# Public_QSGMII_ETHERNET_POWER.net
KiCad netlist of a schematic drawn in Altium Designer
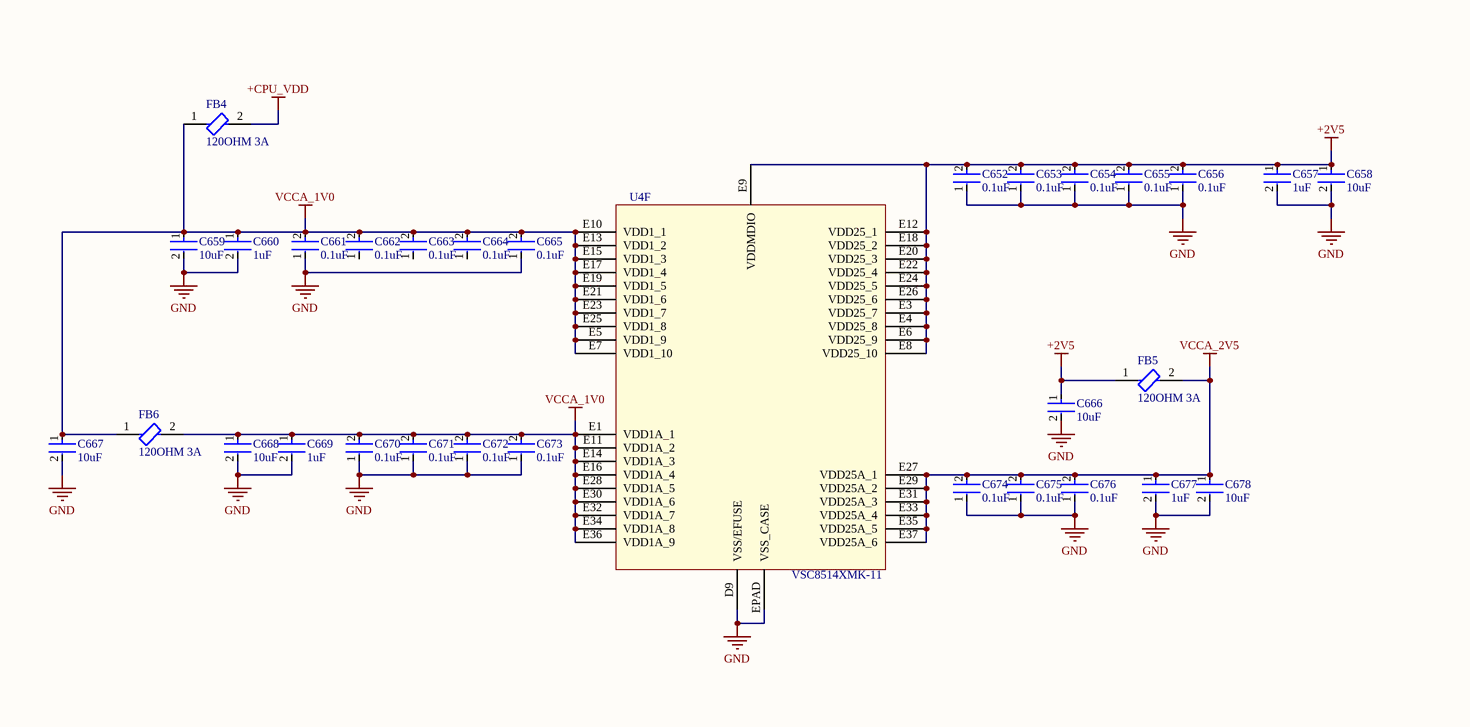
[diagram p0: Public_QSGMII_ETHERNET_POWER.SchDoc, left]
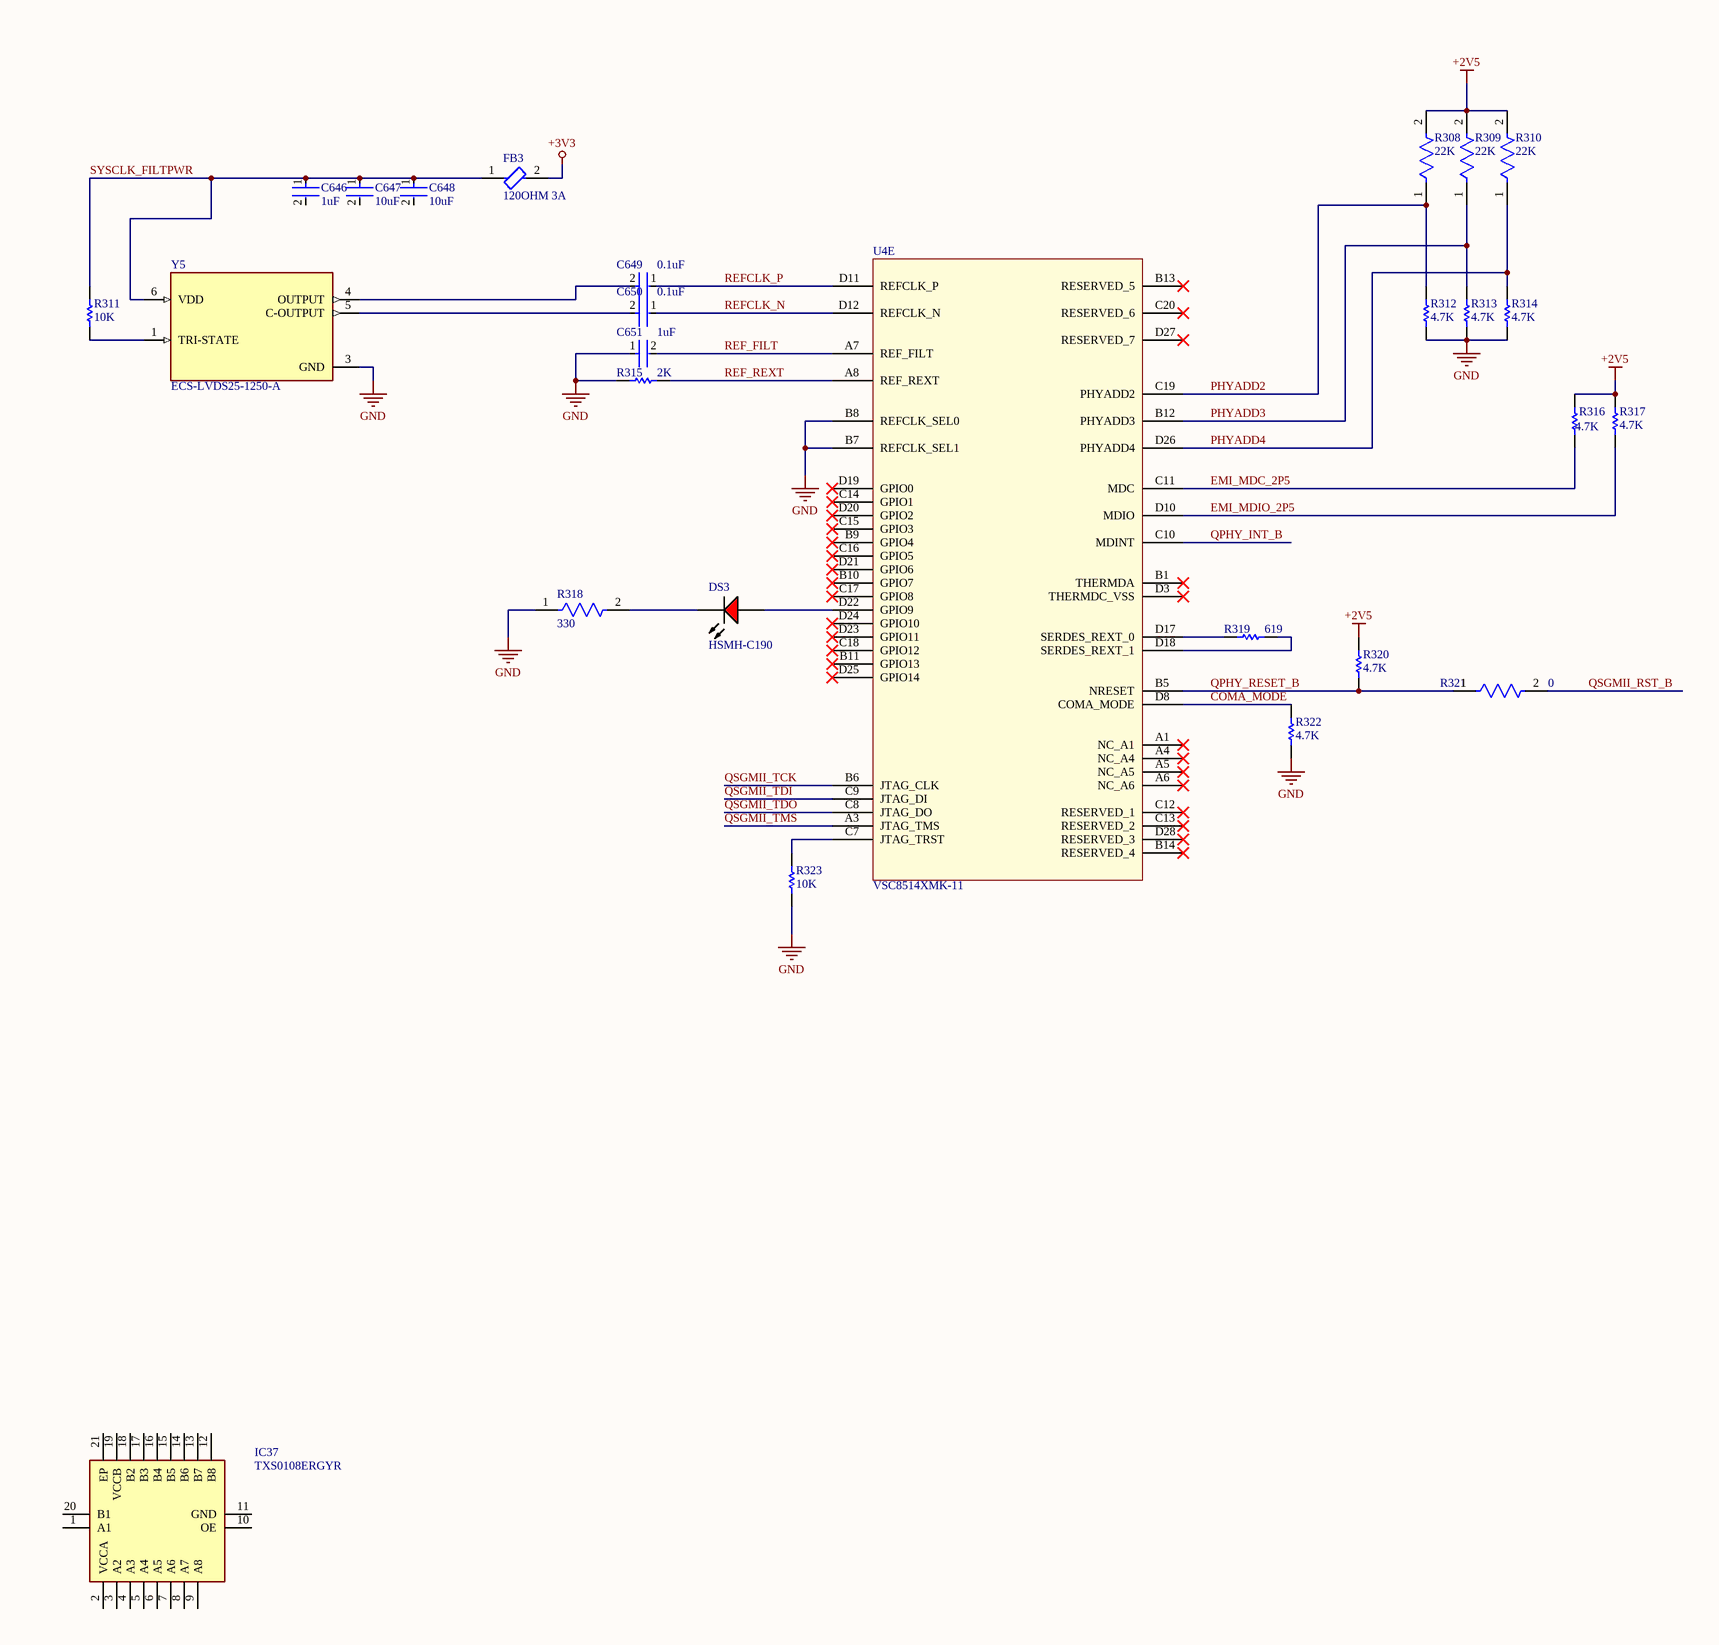
[diagram p1: Public_QSGMII_ETHERNET_POWER.SchDoc, right]

(export (version "E")
  (design (tool "Eeschema 10.0.6"))
  (components
    (comp (ref "C646")
      (value "1uF")
      (footprint "FP-GRM15-0_1-MFG")
      (description "CAP CER 1UF 10V X5R 0402")
      (fields
        (field (name "OCTOPART") "https://octopart.com/grm155r61a105ke15d-murata-197442")
        (field (name "MANUFACTURER PART NUMBER") "GRM155R61A105KE15D")
      )
      (libsource (lib "Altium Content Vault") (part "02cd4be3c70576c341d710602a673aa"))
    )
    (comp (ref "C647")
      (value "10uF")
      (footprint "FP-C0805C-DG-MFG")
      (description "CAP CER 10UF 10V X5R 0805")
      (fields (field (name "TOLERANCE") "10%") (field (name "MANUFACTURER PART NUMBER") "C0805C106K8PACTU"))
      (libsource (lib "Altium Content Vault") (part "11868f565c42a9108669ba33697ecf6"))
    )
    (comp (ref "C648")
      (value "10uF")
      (footprint "FP-C0805C-DG-MFG")
      (description "CAP CER 10UF 10V X5R 0805")
      (fields (field (name "TOLERANCE") "10%") (field (name "MANUFACTURER PART NUMBER") "C0805C106K8PACTU"))
      (libsource (lib "Altium Content Vault") (part "11868f565c42a9108669ba33697ecf6"))
    )
    (comp (ref "C649")
      (value "0.1uF")
      (footprint "FP-GRM15-MFG")
      (description "CAP CER 0.1UF 16V X7R 0402")
      (fields (field (name "MANUFACTURER PART NUMBER") "GRM155R71C104KA88D") (field (name "TOLERANCE") "10%"))
      (libsource (lib "Altium Content Vault") (part "236180d848d6139a670b325ea6854c9"))
    )
    (comp (ref "C650")
      (value "0.1uF")
      (footprint "FP-GRM15-MFG")
      (description "CAP CER 0.1UF 16V X7R 0402")
      (fields (field (name "MANUFACTURER PART NUMBER") "GRM155R71C104KA88D") (field (name "TOLERANCE") "10%"))
      (libsource (lib "Altium Content Vault") (part "236180d848d6139a670b325ea6854c9"))
    )
    (comp (ref "C651")
      (value "1uF")
      (footprint "FP-GRM15-0_1-MFG")
      (description "CAP CER 1UF 10V X5R 0402")
      (fields
        (field (name "OCTOPART") "https://octopart.com/grm155r61a105ke15d-murata-197442")
        (field (name "MANUFACTURER PART NUMBER") "GRM155R61A105KE15D")
      )
      (libsource (lib "Altium Content Vault") (part "02cd4be3c70576c341d710602a673aa"))
    )
    (comp (ref "C652")
      (value "0.1uF")
      (footprint "FP-GRM15-MFG")
      (description "CAP CER 0.1UF 16V X7R 0402")
      (fields (field (name "MANUFACTURER PART NUMBER") "GRM155R71C104KA88D") (field (name "TOLERANCE") "10%"))
      (libsource (lib "Altium Content Vault") (part "236180d848d6139a670b325ea6854c9"))
    )
    (comp (ref "C653")
      (value "0.1uF")
      (footprint "FP-GRM15-MFG")
      (description "CAP CER 0.1UF 16V X7R 0402")
      (fields (field (name "MANUFACTURER PART NUMBER") "GRM155R71C104KA88D") (field (name "TOLERANCE") "10%"))
      (libsource (lib "Altium Content Vault") (part "236180d848d6139a670b325ea6854c9"))
    )
    (comp (ref "C654")
      (value "0.1uF")
      (footprint "FP-GRM15-MFG")
      (description "CAP CER 0.1UF 16V X7R 0402")
      (fields (field (name "MANUFACTURER PART NUMBER") "GRM155R71C104KA88D") (field (name "TOLERANCE") "10%"))
      (libsource (lib "Altium Content Vault") (part "236180d848d6139a670b325ea6854c9"))
    )
    (comp (ref "C655")
      (value "0.1uF")
      (footprint "FP-GRM15-MFG")
      (description "CAP CER 0.1UF 16V X7R 0402")
      (fields (field (name "MANUFACTURER PART NUMBER") "GRM155R71C104KA88D") (field (name "TOLERANCE") "10%"))
      (libsource (lib "Altium Content Vault") (part "236180d848d6139a670b325ea6854c9"))
    )
    (comp (ref "C656")
      (value "0.1uF")
      (footprint "FP-GRM15-MFG")
      (description "CAP CER 0.1UF 16V X7R 0402")
      (fields (field (name "MANUFACTURER PART NUMBER") "GRM155R71C104KA88D") (field (name "TOLERANCE") "10%"))
      (libsource (lib "Altium Content Vault") (part "236180d848d6139a670b325ea6854c9"))
    )
    (comp (ref "C657")
      (value "1uF")
      (footprint "FP-GRM15-0_1-MFG")
      (description "CAP CER 1UF 10V X5R 0402")
      (fields
        (field (name "OCTOPART") "https://octopart.com/grm155r61a105ke15d-murata-197442")
        (field (name "MANUFACTURER PART NUMBER") "GRM155R61A105KE15D")
      )
      (libsource (lib "Altium Content Vault") (part "02cd4be3c70576c341d710602a673aa"))
    )
    (comp (ref "C658")
      (value "10uF")
      (footprint "FP-C0805C-DG-MFG")
      (description "CAP CER 10UF 10V X5R 0805")
      (fields (field (name "TOLERANCE") "10%") (field (name "MANUFACTURER PART NUMBER") "C0805C106K8PACTU"))
      (libsource (lib "Altium Content Vault") (part "11868f565c42a9108669ba33697ecf6"))
    )
    (comp (ref "C659")
      (value "10uF")
      (footprint "FP-C0805C-DG-MFG")
      (description "CAP CER 10UF 10V X5R 0805")
      (fields (field (name "TOLERANCE") "10%") (field (name "MANUFACTURER PART NUMBER") "C0805C106K8PACTU"))
      (libsource (lib "Altium Content Vault") (part "11868f565c42a9108669ba33697ecf6"))
    )
    (comp (ref "C660")
      (value "1uF")
      (footprint "FP-GRM15-0_1-MFG")
      (description "CAP CER 1UF 10V X5R 0402")
      (fields
        (field (name "OCTOPART") "https://octopart.com/grm155r61a105ke15d-murata-197442")
        (field (name "MANUFACTURER PART NUMBER") "GRM155R61A105KE15D")
      )
      (libsource (lib "Altium Content Vault") (part "02cd4be3c70576c341d710602a673aa"))
    )
    (comp (ref "C661")
      (value "0.1uF")
      (footprint "FP-GRM15-MFG")
      (description "CAP CER 0.1UF 16V X7R 0402")
      (fields (field (name "MANUFACTURER PART NUMBER") "GRM155R71C104KA88D") (field (name "TOLERANCE") "10%"))
      (libsource (lib "Altium Content Vault") (part "236180d848d6139a670b325ea6854c9"))
    )
    (comp (ref "C662")
      (value "0.1uF")
      (footprint "FP-GRM15-MFG")
      (description "CAP CER 0.1UF 16V X7R 0402")
      (fields (field (name "MANUFACTURER PART NUMBER") "GRM155R71C104KA88D") (field (name "TOLERANCE") "10%"))
      (libsource (lib "Altium Content Vault") (part "236180d848d6139a670b325ea6854c9"))
    )
    (comp (ref "C663")
      (value "0.1uF")
      (footprint "FP-GRM15-MFG")
      (description "CAP CER 0.1UF 16V X7R 0402")
      (fields (field (name "MANUFACTURER PART NUMBER") "GRM155R71C104KA88D") (field (name "TOLERANCE") "10%"))
      (libsource (lib "Altium Content Vault") (part "236180d848d6139a670b325ea6854c9"))
    )
    (comp (ref "C664")
      (value "0.1uF")
      (footprint "FP-GRM15-MFG")
      (description "CAP CER 0.1UF 16V X7R 0402")
      (fields (field (name "MANUFACTURER PART NUMBER") "GRM155R71C104KA88D") (field (name "TOLERANCE") "10%"))
      (libsource (lib "Altium Content Vault") (part "236180d848d6139a670b325ea6854c9"))
    )
    (comp (ref "C665")
      (value "0.1uF")
      (footprint "FP-GRM15-MFG")
      (description "CAP CER 0.1UF 16V X7R 0402")
      (fields (field (name "MANUFACTURER PART NUMBER") "GRM155R71C104KA88D") (field (name "TOLERANCE") "10%"))
      (libsource (lib "Altium Content Vault") (part "236180d848d6139a670b325ea6854c9"))
    )
    (comp (ref "C666")
      (value "10uF")
      (footprint "FP-C0805C-DG-MFG")
      (description "CAP CER 10UF 10V X5R 0805")
      (fields (field (name "TOLERANCE") "10%") (field (name "MANUFACTURER PART NUMBER") "C0805C106K8PACTU"))
      (libsource (lib "Altium Content Vault") (part "11868f565c42a9108669ba33697ecf6"))
    )
    (comp (ref "C667")
      (value "10uF")
      (footprint "FP-C0805C-DG-MFG")
      (description "CAP CER 10UF 10V X5R 0805")
      (fields (field (name "TOLERANCE") "10%") (field (name "MANUFACTURER PART NUMBER") "C0805C106K8PACTU"))
      (libsource (lib "Altium Content Vault") (part "11868f565c42a9108669ba33697ecf6"))
    )
    (comp (ref "C668")
      (value "10uF")
      (footprint "FP-C0805C-DG-MFG")
      (description "CAP CER 10UF 10V X5R 0805")
      (fields (field (name "TOLERANCE") "10%") (field (name "MANUFACTURER PART NUMBER") "C0805C106K8PACTU"))
      (libsource (lib "Altium Content Vault") (part "11868f565c42a9108669ba33697ecf6"))
    )
    (comp (ref "C669")
      (value "1uF")
      (footprint "FP-GRM15-0_1-MFG")
      (description "CAP CER 1UF 10V X5R 0402")
      (fields
        (field (name "OCTOPART") "https://octopart.com/grm155r61a105ke15d-murata-197442")
        (field (name "MANUFACTURER PART NUMBER") "GRM155R61A105KE15D")
      )
      (libsource (lib "Altium Content Vault") (part "02cd4be3c70576c341d710602a673aa"))
    )
    (comp (ref "C670")
      (value "0.1uF")
      (footprint "FP-GRM15-MFG")
      (description "CAP CER 0.1UF 16V X7R 0402")
      (fields (field (name "MANUFACTURER PART NUMBER") "GRM155R71C104KA88D") (field (name "TOLERANCE") "10%"))
      (libsource (lib "Altium Content Vault") (part "236180d848d6139a670b325ea6854c9"))
    )
    (comp (ref "C671")
      (value "0.1uF")
      (footprint "FP-GRM15-MFG")
      (description "CAP CER 0.1UF 16V X7R 0402")
      (fields (field (name "MANUFACTURER PART NUMBER") "GRM155R71C104KA88D") (field (name "TOLERANCE") "10%"))
      (libsource (lib "Altium Content Vault") (part "236180d848d6139a670b325ea6854c9"))
    )
    (comp (ref "C672")
      (value "0.1uF")
      (footprint "FP-GRM15-MFG")
      (description "CAP CER 0.1UF 16V X7R 0402")
      (fields (field (name "MANUFACTURER PART NUMBER") "GRM155R71C104KA88D") (field (name "TOLERANCE") "10%"))
      (libsource (lib "Altium Content Vault") (part "236180d848d6139a670b325ea6854c9"))
    )
    (comp (ref "C673")
      (value "0.1uF")
      (footprint "FP-GRM15-MFG")
      (description "CAP CER 0.1UF 16V X7R 0402")
      (fields (field (name "MANUFACTURER PART NUMBER") "GRM155R71C104KA88D") (field (name "TOLERANCE") "10%"))
      (libsource (lib "Altium Content Vault") (part "236180d848d6139a670b325ea6854c9"))
    )
    (comp (ref "C674")
      (value "0.1uF")
      (footprint "FP-GRM15-MFG")
      (description "CAP CER 0.1UF 16V X7R 0402")
      (fields (field (name "MANUFACTURER PART NUMBER") "GRM155R71C104KA88D") (field (name "TOLERANCE") "10%"))
      (libsource (lib "Altium Content Vault") (part "236180d848d6139a670b325ea6854c9"))
    )
    (comp (ref "C675")
      (value "0.1uF")
      (footprint "FP-GRM15-MFG")
      (description "CAP CER 0.1UF 16V X7R 0402")
      (fields (field (name "MANUFACTURER PART NUMBER") "GRM155R71C104KA88D") (field (name "TOLERANCE") "10%"))
      (libsource (lib "Altium Content Vault") (part "236180d848d6139a670b325ea6854c9"))
    )
    (comp (ref "C676")
      (value "0.1uF")
      (footprint "FP-GRM15-MFG")
      (description "CAP CER 0.1UF 16V X7R 0402")
      (fields (field (name "MANUFACTURER PART NUMBER") "GRM155R71C104KA88D") (field (name "TOLERANCE") "10%"))
      (libsource (lib "Altium Content Vault") (part "236180d848d6139a670b325ea6854c9"))
    )
    (comp (ref "C677")
      (value "1uF")
      (footprint "FP-GRM15-0_1-MFG")
      (description "CAP CER 1UF 10V X5R 0402")
      (fields
        (field (name "OCTOPART") "https://octopart.com/grm155r61a105ke15d-murata-197442")
        (field (name "MANUFACTURER PART NUMBER") "GRM155R61A105KE15D")
      )
      (libsource (lib "Altium Content Vault") (part "02cd4be3c70576c341d710602a673aa"))
    )
    (comp (ref "C678")
      (value "10uF")
      (footprint "FP-C0805C-DG-MFG")
      (description "CAP CER 10UF 10V X5R 0805")
      (fields (field (name "TOLERANCE") "10%") (field (name "MANUFACTURER PART NUMBER") "C0805C106K8PACTU"))
      (libsource (lib "Altium Content Vault") (part "11868f565c42a9108669ba33697ecf6"))
    )
    (comp (ref "DS3")
      (value "HSMH-C190")
      (footprint "AVAG-HSMX-C190_V")
      (description "LED Uni-Color Red, 65 mW, 20 mA, -40 to 85 degC, 2-Pin SMD, RoHS, Tape and Reel")
      (libsource (lib "Altium Content Vault") (part "LED-RED-AK-2"))
    )
    (comp (ref "FB3")
      (value "120OHM 3A")
      (footprint "FP-BLM18-0_15-t0_5-d1_2-MFG")
      (description "Chip Ferrite Bead, 0603, 120Ω @ 100MHz, 25%, 0.025Ω, 3A")
      (fields (field (name "TOLERANCE") "25%"))
      (libsource (lib "Altium Content Vault") (part "5f30dd21d616792df468990f7003faa"))
    )
    (comp (ref "FB4")
      (value "120OHM 3A")
      (footprint "FP-BLM18-0_15-t0_5-d1_2-MFG")
      (description "Chip Ferrite Bead, 0603, 120Ω @ 100MHz, 25%, 0.025Ω, 3A")
      (fields (field (name "TOLERANCE") "25%"))
      (libsource (lib "Altium Content Vault") (part "5f30dd21d616792df468990f7003faa"))
    )
    (comp (ref "FB5")
      (value "120OHM 3A")
      (footprint "FP-BLM18-0_15-t0_5-d1_2-MFG")
      (description "Chip Ferrite Bead, 0603, 120Ω @ 100MHz, 25%, 0.025Ω, 3A")
      (fields (field (name "TOLERANCE") "25%"))
      (libsource (lib "Altium Content Vault") (part "5f30dd21d616792df468990f7003faa"))
    )
    (comp (ref "FB6")
      (value "120OHM 3A")
      (footprint "FP-BLM18-0_15-t0_5-d1_2-MFG")
      (description "Chip Ferrite Bead, 0603, 120Ω @ 100MHz, 25%, 0.025Ω, 3A")
      (fields (field (name "TOLERANCE") "25%"))
      (libsource (lib "Altium Content Vault") (part "5f30dd21d616792df468990f7003faa"))
    )
    (comp (ref "IC37")
      (value "TXS0108ERGYR")
      (footprint "SamacSys:SN74LVC541ARGYR")
      (description "Integrated Circuit")
      (fields (field (name "MOUSER PART NUMBER") "595-TXS0108ERGYR"))
      (libsource (lib "SamacSys") (part "TXS0108ERGYR"))
    )
    (comp (ref "R308")
      (value "22K")
      (footprint "FP-ERJ2RK-MFG")
      (description "RES SMD 22K OHM 1% 1/10W 0402")
      (fields (field (name "TOLERANCE") "1%"))
      (libsource (lib "Altium Content Vault") (part "1029c3af85768c4190bb7ad29bc67b5"))
    )
    (comp (ref "R309")
      (value "22K")
      (footprint "FP-ERJ2RK-MFG")
      (description "RES SMD 22K OHM 1% 1/10W 0402")
      (fields (field (name "TOLERANCE") "1%"))
      (libsource (lib "Altium Content Vault") (part "1029c3af85768c4190bb7ad29bc67b5"))
    )
    (comp (ref "R310")
      (value "22K")
      (footprint "FP-ERJ2RK-MFG")
      (description "RES SMD 22K OHM 1% 1/10W 0402")
      (fields (field (name "TOLERANCE") "1%"))
      (libsource (lib "Altium Content Vault") (part "1029c3af85768c4190bb7ad29bc67b5"))
    )
    (comp (ref "R311")
      (value "10K")
      (footprint "RESC1005X40X25LL05T05")
      (description "Chip Resistor, 10 KOhm, +/- 1%, 0.1 W, -55 to 155 degC, 0402 (1005 Metric), RoHS, Tape and Reel")
      (fields (field (name "TOLERANCE") "1%") (field (name "MANUFACTURER") "Panasonic"))
      (libsource (lib "Altium Content Vault") (part "RES-2"))
    )
    (comp (ref "R312")
      (value "4.7K")
      (footprint "RESC1005X40X25LL05T05")
      (description "Chip Resistor, 4.7 KOhm, +/- 1%, 0.1 W, -55 to 155 degC, 0402 (1005 Metric), RoHS, Tape and Reel")
      (fields (field (name "TOLERANCE") "1%") (field (name "PARTNUMBER") "ERJ-2RKF4701X"))
      (libsource (lib "Altium Content Vault") (part "RES-2"))
    )
    (comp (ref "R313")
      (value "4.7K")
      (footprint "RESC1005X40X25LL05T05")
      (description "Chip Resistor, 4.7 KOhm, +/- 1%, 0.1 W, -55 to 155 degC, 0402 (1005 Metric), RoHS, Tape and Reel")
      (fields (field (name "TOLERANCE") "1%") (field (name "PARTNUMBER") "ERJ-2RKF4701X"))
      (libsource (lib "Altium Content Vault") (part "RES-2"))
    )
    (comp (ref "R314")
      (value "4.7K")
      (footprint "RESC1005X40X25LL05T05")
      (description "Chip Resistor, 4.7 KOhm, +/- 1%, 0.1 W, -55 to 155 degC, 0402 (1005 Metric), RoHS, Tape and Reel")
      (fields (field (name "TOLERANCE") "1%") (field (name "PARTNUMBER") "ERJ-2RKF4701X"))
      (libsource (lib "Altium Content Vault") (part "RES-2"))
    )
    (comp (ref "R315")
      (value "2K")
      (footprint "RESC1005X40X25LL10T10")
      (fields (field (name "MANUFACTURER") "Panasonic") (field (name "PART NUMBER") "ERA-2AEB202X"))
      (libsource (lib "Altium Content Vault") (part "RES"))
    )
    (comp (ref "R316")
      (value "4.7K")
      (footprint "RESC1005X40X25LL05T05")
      (description "Chip Resistor, 4.7 KOhm, +/- 1%, 0.1 W, -55 to 155 degC, 0402 (1005 Metric), RoHS, Tape and Reel")
      (fields (field (name "TOLERANCE") "1%") (field (name "PARTNUMBER") "ERJ-2RKF4701X"))
      (libsource (lib "Altium Content Vault") (part "RES-2"))
    )
    (comp (ref "R317")
      (value "4.7K")
      (footprint "RESC1005X40X25LL05T05")
      (description "Chip Resistor, 4.7 KOhm, +/- 1%, 0.1 W, -55 to 155 degC, 0402 (1005 Metric), RoHS, Tape and Reel")
      (fields (field (name "TOLERANCE") "1%") (field (name "PARTNUMBER") "ERJ-2RKF4701X"))
      (libsource (lib "Altium Content Vault") (part "RES-2"))
    )
    (comp (ref "R318")
      (value "330")
      (footprint "FP-CRCW0603-e3-MFG")
      (description "RES Thick Film, 330Ω, 1%, 0.1W, 100ppm/°C, 0603")
      (fields (field (name "TOLERANCE") "1%"))
      (libsource (lib "Altium Content Vault") (part "1029c3af85768c4190bb7ad29bc67b5"))
    )
    (comp (ref "R319")
      (value "619")
      (footprint "RESC1005X40X25ML05T05")
      (fields (field (name "PART NUMBER") "ERJ-2RKF6193X") (field (name "MANUFACTURER") "Panasonic"))
      (libsource (lib "Altium Content Vault") (part "RES"))
    )
    (comp (ref "R320")
      (value "4.7K")
      (footprint "RESC1005X40X25LL05T05")
      (description "Chip Resistor, 4.7 KOhm, +/- 1%, 0.1 W, -55 to 155 degC, 0402 (1005 Metric), RoHS, Tape and Reel")
      (fields (field (name "TOLERANCE") "1%") (field (name "PARTNUMBER") "ERJ-2RKF4701X"))
      (libsource (lib "Altium Content Vault") (part "RES-2"))
    )
    (comp (ref "R321")
      (value "0")
      (footprint "FP-CRCW0402-e3-IPC_C")
      (description "RES Thick Film, 0Ω, 0.063W, 0402")
      (fields (field (name "TOLERANCE") "5%"))
      (libsource (lib "Altium Content Vault") (part "1029c3af85768c4190bb7ad29bc67b5"))
    )
    (comp (ref "R322")
      (value "4.7K")
      (footprint "RESC1005X40X25LL05T05")
      (description "Chip Resistor, 4.7 KOhm, +/- 1%, 0.1 W, -55 to 155 degC, 0402 (1005 Metric), RoHS, Tape and Reel")
      (fields (field (name "TOLERANCE") "1%") (field (name "PARTNUMBER") "ERJ-2RKF4701X"))
      (libsource (lib "Altium Content Vault") (part "RES-2"))
    )
    (comp (ref "R323")
      (value "10K")
      (footprint "RESC1005X40X25LL05T05")
      (description "Chip Resistor, 10 KOhm, +/- 1%, 0.1 W, -55 to 155 degC, 0402 (1005 Metric), RoHS, Tape and Reel")
      (fields (field (name "TOLERANCE") "1%") (field (name "MANUFACTURER") "Panasonic"))
      (libsource (lib "Altium Content Vault") (part "RES-2"))
    )
    (comp (ref "U4")
      (value "VSC8514XMK-11")
      (footprint "QFN138_12X12X0P85_MCH")
      (description "No Description Available")
      (fields (field (name "COPYRIGHT") "Copyright (C) 2018 Accelerated Designs. All rights reserved"))
      (libsource (lib "VSC8514XMK-11") (part "VSC8514XMK-11"))
    )
    (comp (ref "Y5")
      (value "ECS-LVDS25-1250-A")
      (footprint "ECS-LVDS25-1250-A:OSC_ECS-LVDS25-1250-A")
      (description "Low Voltage Differential Signaling SMD LVDS oscillators.")
      (fields (field (name "MF") "{'manufacturer': u'ECS Inc.'}"))
      (libsource (lib "*") (part "ECS-LVDS25-1250-A"))
    )
  )
  (nets
    (net (code "1") (name "+2V5") (class "Default")
      (node (ref "C652") (pin "2") (pinfunction "2_2") (pintype "passive"))
      (node (ref "C653") (pin "2") (pinfunction "2_2") (pintype "passive"))
      (node (ref "C654") (pin "2") (pinfunction "2_2") (pintype "passive"))
      (node (ref "C655") (pin "2") (pinfunction "2_2") (pintype "passive"))
      (node (ref "C656") (pin "2") (pinfunction "2_2") (pintype "passive"))
      (node (ref "C657") (pin "1") (pinfunction "1_1") (pintype "passive"))
      (node (ref "C658") (pin "1") (pinfunction "1_1") (pintype "passive"))
      (node (ref "C666") (pin "1") (pinfunction "1_1") (pintype "passive"))
      (node (ref "FB5") (pin "1") (pinfunction "1_1") (pintype "passive"))
      (node (ref "R308") (pin "2") (pinfunction "2_2") (pintype "passive"))
      (node (ref "R309") (pin "2") (pinfunction "2_2") (pintype "passive"))
      (node (ref "R310") (pin "2") (pinfunction "2_2") (pintype "passive"))
      (node (ref "R316") (pin "2") (pinfunction "2_2") (pintype "passive"))
      (node (ref "R317") (pin "2") (pinfunction "2_2") (pintype "passive"))
      (node (ref "R320") (pin "2") (pinfunction "2_2") (pintype "passive"))
      (node (ref "U4") (pin "E12") (pinfunction "VDD25_1_E12") (pintype "passive"))
      (node (ref "U4") (pin "E18") (pinfunction "VDD25_2_E18") (pintype "passive"))
      (node (ref "U4") (pin "E20") (pinfunction "VDD25_3_E20") (pintype "passive"))
      (node (ref "U4") (pin "E22") (pinfunction "VDD25_4_E22") (pintype "passive"))
      (node (ref "U4") (pin "E24") (pinfunction "VDD25_5_E24") (pintype "passive"))
      (node (ref "U4") (pin "E26") (pinfunction "VDD25_6_E26") (pintype "passive"))
      (node (ref "U4") (pin "E3") (pinfunction "VDD25_7_E3") (pintype "passive"))
      (node (ref "U4") (pin "E4") (pinfunction "VDD25_8_E4") (pintype "passive"))
      (node (ref "U4") (pin "E6") (pinfunction "VDD25_9_E6") (pintype "passive"))
      (node (ref "U4") (pin "E8") (pinfunction "VDD25_10_E8") (pintype "passive"))
      (node (ref "U4") (pin "E9") (pinfunction "VDDMDIO_E9") (pintype "passive"))
    )
    (net (code "2") (name "+3V3") (class "Default")
      (node (ref "FB3") (pin "2") (pinfunction "2_2") (pintype "passive"))
    )
    (net (code "3") (name "+CPU_VDD") (class "Default")
      (node (ref "FB4") (pin "2") (pinfunction "2_2") (pintype "passive"))
    )
    (net (code "4") (name "/COMA_MODE") (class "Default")
      (node (ref "R322") (pin "2") (pinfunction "2_2") (pintype "passive"))
      (node (ref "U4") (pin "D8") (pinfunction "COMA_MODE_D8") (pintype "passive"))
    )
    (net (code "5") (name "/EMI_MDC_2P5") (class "Default")
      (node (ref "R316") (pin "1") (pinfunction "1_1") (pintype "passive"))
      (node (ref "U4") (pin "C11") (pinfunction "MDC_C11") (pintype "passive"))
    )
    (net (code "6") (name "/EMI_MDIO_2P5") (class "Default")
      (node (ref "R317") (pin "1") (pinfunction "1_1") (pintype "passive"))
      (node (ref "U4") (pin "D10") (pinfunction "MDIO_D10") (pintype "passive"))
    )
    (net (code "7") (name "/PHYADD2") (class "Default")
      (node (ref "R308") (pin "1") (pinfunction "1_1") (pintype "passive"))
      (node (ref "R312") (pin "2") (pinfunction "2_2") (pintype "passive"))
      (node (ref "U4") (pin "C19") (pinfunction "PHYADD2_C19") (pintype "passive"))
    )
    (net (code "8") (name "/PHYADD3") (class "Default")
      (node (ref "R309") (pin "1") (pinfunction "1_1") (pintype "passive"))
      (node (ref "R313") (pin "2") (pinfunction "2_2") (pintype "passive"))
      (node (ref "U4") (pin "B12") (pinfunction "PHYADD3_B12") (pintype "passive"))
    )
    (net (code "9") (name "/PHYADD4") (class "Default")
      (node (ref "R310") (pin "1") (pinfunction "1_1") (pintype "passive"))
      (node (ref "R314") (pin "2") (pinfunction "2_2") (pintype "passive"))
      (node (ref "U4") (pin "D26") (pinfunction "PHYADD4_D26") (pintype "passive"))
    )
    (net (code "10") (name "/QPHY_INT_B") (class "Default")
      (node (ref "U4") (pin "C10") (pinfunction "MDINT_C10") (pintype "passive"))
    )
    (net (code "11") (name "/QPHY_RESET_B") (class "Default")
      (node (ref "R320") (pin "1") (pinfunction "1_1") (pintype "passive"))
      (node (ref "R321") (pin "1") (pinfunction "1_1") (pintype "passive"))
      (node (ref "U4") (pin "B5") (pinfunction "NRESET_B5") (pintype "passive"))
    )
    (net (code "12") (name "/QSGMII_RST_B") (class "Default")
      (node (ref "R321") (pin "2") (pinfunction "2_2") (pintype "passive"))
    )
    (net (code "13") (name "/QSGMII_TCK") (class "Default")
      (node (ref "U4") (pin "B6") (pinfunction "JTAG_CLK_B6") (pintype "passive"))
    )
    (net (code "14") (name "/QSGMII_TDI") (class "Default")
      (node (ref "U4") (pin "C9") (pinfunction "JTAG_DI_C9") (pintype "passive"))
    )
    (net (code "15") (name "/QSGMII_TDO") (class "Default")
      (node (ref "U4") (pin "C8") (pinfunction "JTAG_DO_C8") (pintype "passive"))
    )
    (net (code "16") (name "/QSGMII_TMS") (class "Default")
      (node (ref "U4") (pin "A3") (pinfunction "JTAG_TMS_A3") (pintype "passive"))
    )
    (net (code "17") (name "/REFCLK_N") (class "Default")
      (node (ref "C650") (pin "1") (pinfunction "1_1") (pintype "passive"))
      (node (ref "U4") (pin "D12") (pinfunction "REFCLK_N_D12") (pintype "passive"))
    )
    (net (code "18") (name "/REFCLK_P") (class "Default")
      (node (ref "C649") (pin "1") (pinfunction "1_1") (pintype "passive"))
      (node (ref "U4") (pin "D11") (pinfunction "REFCLK_P_D11") (pintype "passive"))
    )
    (net (code "19") (name "/REF_FILT") (class "Default")
      (node (ref "C651") (pin "2") (pinfunction "2_2") (pintype "passive"))
      (node (ref "U4") (pin "A7") (pinfunction "REF_FILT_A7") (pintype "passive"))
    )
    (net (code "20") (name "/REF_REXT") (class "Default")
      (node (ref "R315") (pin "2") (pinfunction "2_2") (pintype "passive"))
      (node (ref "U4") (pin "A8") (pinfunction "REF_REXT_A8") (pintype "passive"))
    )
    (net (code "21") (name "/SYSCLK_FILTPWR") (class "Default")
      (node (ref "C646") (pin "1") (pinfunction "1_1") (pintype "passive"))
      (node (ref "C647") (pin "1") (pinfunction "1_1") (pintype "passive"))
      (node (ref "C648") (pin "1") (pinfunction "1_1") (pintype "passive"))
      (node (ref "FB3") (pin "1") (pinfunction "1_1") (pintype "passive"))
      (node (ref "R311") (pin "2") (pinfunction "2_2") (pintype "passive"))
      (node (ref "Y5") (pin "6") (pinfunction "VDD_6") (pintype "input"))
    )
    (net (code "22") (name "GND") (class "Default")
      (node (ref "C651") (pin "1") (pinfunction "1_1") (pintype "passive"))
      (node (ref "C652") (pin "1") (pinfunction "1_1") (pintype "passive"))
      (node (ref "C653") (pin "1") (pinfunction "1_1") (pintype "passive"))
      (node (ref "C654") (pin "1") (pinfunction "1_1") (pintype "passive"))
      (node (ref "C655") (pin "1") (pinfunction "1_1") (pintype "passive"))
      (node (ref "C656") (pin "1") (pinfunction "1_1") (pintype "passive"))
      (node (ref "C657") (pin "2") (pinfunction "2_2") (pintype "passive"))
      (node (ref "C658") (pin "2") (pinfunction "2_2") (pintype "passive"))
      (node (ref "C659") (pin "2") (pinfunction "2_2") (pintype "passive"))
      (node (ref "C660") (pin "2") (pinfunction "2_2") (pintype "passive"))
      (node (ref "C661") (pin "1") (pinfunction "1_1") (pintype "passive"))
      (node (ref "C665") (pin "1") (pinfunction "1_1") (pintype "passive"))
      (node (ref "C666") (pin "2") (pinfunction "2_2") (pintype "passive"))
      (node (ref "C667") (pin "2") (pinfunction "2_2") (pintype "passive"))
      (node (ref "C668") (pin "2") (pinfunction "2_2") (pintype "passive"))
      (node (ref "C669") (pin "2") (pinfunction "2_2") (pintype "passive"))
      (node (ref "C670") (pin "1") (pinfunction "1_1") (pintype "passive"))
      (node (ref "C671") (pin "1") (pinfunction "1_1") (pintype "passive"))
      (node (ref "C672") (pin "1") (pinfunction "1_1") (pintype "passive"))
      (node (ref "C673") (pin "1") (pinfunction "1_1") (pintype "passive"))
      (node (ref "C674") (pin "1") (pinfunction "1_1") (pintype "passive"))
      (node (ref "C675") (pin "1") (pinfunction "1_1") (pintype "passive"))
      (node (ref "C676") (pin "1") (pinfunction "1_1") (pintype "passive"))
      (node (ref "C677") (pin "2") (pinfunction "2_2") (pintype "passive"))
      (node (ref "C678") (pin "2") (pinfunction "2_2") (pintype "passive"))
      (node (ref "R312") (pin "1") (pinfunction "1_1") (pintype "passive"))
      (node (ref "R313") (pin "1") (pinfunction "1_1") (pintype "passive"))
      (node (ref "R314") (pin "1") (pinfunction "1_1") (pintype "passive"))
      (node (ref "R315") (pin "1") (pinfunction "1_1") (pintype "passive"))
      (node (ref "R318") (pin "1") (pinfunction "1_1") (pintype "passive"))
      (node (ref "R322") (pin "1") (pinfunction "1_1") (pintype "passive"))
      (node (ref "R323") (pin "1") (pinfunction "1_1") (pintype "passive"))
      (node (ref "U4") (pin "B7") (pinfunction "REFCLK_SEL1_B7") (pintype "passive"))
      (node (ref "U4") (pin "B8") (pinfunction "REFCLK_SEL0_B8") (pintype "passive"))
      (node (ref "U4") (pin "D9") (pinfunction "VSS/EFUSE_D9") (pintype "passive"))
      (node (ref "U4") (pin "EPAD") (pinfunction "VSS_CASE_EPAD") (pintype "passive"))
      (node (ref "Y5") (pin "3") (pinfunction "GND_3") (pintype "power_in"))
    )
    (net (code "23") (name "Net-(DS3-A)") (class "Default")
      (node (ref "DS3") (pin "1") (pinfunction "A_1") (pintype "passive"))
      (node (ref "U4") (pin "D22") (pinfunction "GPIO9_D22") (pintype "passive"))
    )
    (net (code "24") (name "Net-(DS3-K)") (class "Default")
      (node (ref "DS3") (pin "2") (pinfunction "K_2") (pintype "passive"))
      (node (ref "R318") (pin "2") (pinfunction "2_2") (pintype "passive"))
    )
    (net (code "25") (name "Net-(U4E-JTAG_TRST)") (class "Default")
      (node (ref "R323") (pin "2") (pinfunction "2_2") (pintype "passive"))
      (node (ref "U4") (pin "C7") (pinfunction "JTAG_TRST_C7") (pintype "passive"))
    )
    (net (code "26") (name "Net-(U4E-SERDES_REXT_0)") (class "Default")
      (node (ref "R319") (pin "1") (pinfunction "1_1") (pintype "passive"))
      (node (ref "U4") (pin "D17") (pinfunction "SERDES_REXT_0_D17") (pintype "passive"))
    )
    (net (code "27") (name "Net-(U4E-SERDES_REXT_1)") (class "Default")
      (node (ref "R319") (pin "2") (pinfunction "2_2") (pintype "passive"))
      (node (ref "U4") (pin "D18") (pinfunction "SERDES_REXT_1_D18") (pintype "passive"))
    )
    (net (code "28") (name "Net-(Y5-C-OUTPUT)") (class "Default")
      (node (ref "C650") (pin "2") (pinfunction "2_2") (pintype "passive"))
      (node (ref "Y5") (pin "5") (pinfunction "C-OUTPUT_5") (pintype "output"))
    )
    (net (code "29") (name "Net-(Y5-OUTPUT)") (class "Default")
      (node (ref "C649") (pin "2") (pinfunction "2_2") (pintype "passive"))
      (node (ref "Y5") (pin "4") (pinfunction "OUTPUT_4") (pintype "output"))
    )
    (net (code "30") (name "Net-(Y5-TRI-STATE)") (class "Default")
      (node (ref "R311") (pin "1") (pinfunction "1_1") (pintype "passive"))
      (node (ref "Y5") (pin "1") (pinfunction "TRI-STATE_1") (pintype "input"))
    )
    (net (code "31") (name "VCCA_1V0") (class "Default")
      (node (ref "C659") (pin "1") (pinfunction "1_1") (pintype "passive"))
      (node (ref "C660") (pin "1") (pinfunction "1_1") (pintype "passive"))
      (node (ref "C661") (pin "2") (pinfunction "2_2") (pintype "passive"))
      (node (ref "C662") (pin "2") (pinfunction "2_2") (pintype "passive"))
      (node (ref "C663") (pin "2") (pinfunction "2_2") (pintype "passive"))
      (node (ref "C664") (pin "2") (pinfunction "2_2") (pintype "passive"))
      (node (ref "C665") (pin "2") (pinfunction "2_2") (pintype "passive"))
      (node (ref "C667") (pin "1") (pinfunction "1_1") (pintype "passive"))
      (node (ref "C668") (pin "1") (pinfunction "1_1") (pintype "passive"))
      (node (ref "C669") (pin "1") (pinfunction "1_1") (pintype "passive"))
      (node (ref "C670") (pin "2") (pinfunction "2_2") (pintype "passive"))
      (node (ref "C671") (pin "2") (pinfunction "2_2") (pintype "passive"))
      (node (ref "C672") (pin "2") (pinfunction "2_2") (pintype "passive"))
      (node (ref "C673") (pin "2") (pinfunction "2_2") (pintype "passive"))
      (node (ref "FB4") (pin "1") (pinfunction "1_1") (pintype "passive"))
      (node (ref "FB6") (pin "1") (pinfunction "1_1") (pintype "passive"))
      (node (ref "FB6") (pin "2") (pinfunction "2_2") (pintype "passive"))
      (node (ref "U4") (pin "E1") (pinfunction "VDD1A_1_E1") (pintype "passive"))
      (node (ref "U4") (pin "E10") (pinfunction "VDD1_1_E10") (pintype "passive"))
      (node (ref "U4") (pin "E11") (pinfunction "VDD1A_2_E11") (pintype "passive"))
      (node (ref "U4") (pin "E13") (pinfunction "VDD1_2_E13") (pintype "passive"))
      (node (ref "U4") (pin "E14") (pinfunction "VDD1A_3_E14") (pintype "passive"))
      (node (ref "U4") (pin "E15") (pinfunction "VDD1_3_E15") (pintype "passive"))
      (node (ref "U4") (pin "E16") (pinfunction "VDD1A_4_E16") (pintype "passive"))
      (node (ref "U4") (pin "E17") (pinfunction "VDD1_4_E17") (pintype "passive"))
      (node (ref "U4") (pin "E19") (pinfunction "VDD1_5_E19") (pintype "passive"))
      (node (ref "U4") (pin "E21") (pinfunction "VDD1_6_E21") (pintype "passive"))
      (node (ref "U4") (pin "E23") (pinfunction "VDD1_7_E23") (pintype "passive"))
      (node (ref "U4") (pin "E25") (pinfunction "VDD1_8_E25") (pintype "passive"))
      (node (ref "U4") (pin "E28") (pinfunction "VDD1A_5_E28") (pintype "passive"))
      (node (ref "U4") (pin "E30") (pinfunction "VDD1A_6_E30") (pintype "passive"))
      (node (ref "U4") (pin "E32") (pinfunction "VDD1A_7_E32") (pintype "passive"))
      (node (ref "U4") (pin "E34") (pinfunction "VDD1A_8_E34") (pintype "passive"))
      (node (ref "U4") (pin "E36") (pinfunction "VDD1A_9_E36") (pintype "passive"))
      (node (ref "U4") (pin "E5") (pinfunction "VDD1_9_E5") (pintype "passive"))
      (node (ref "U4") (pin "E7") (pinfunction "VDD1_10_E7") (pintype "passive"))
    )
    (net (code "32") (name "VCCA_2V5") (class "Default")
      (node (ref "C674") (pin "2") (pinfunction "2_2") (pintype "passive"))
      (node (ref "C675") (pin "2") (pinfunction "2_2") (pintype "passive"))
      (node (ref "C676") (pin "2") (pinfunction "2_2") (pintype "passive"))
      (node (ref "C677") (pin "1") (pinfunction "1_1") (pintype "passive"))
      (node (ref "C678") (pin "1") (pinfunction "1_1") (pintype "passive"))
      (node (ref "FB5") (pin "2") (pinfunction "2_2") (pintype "passive"))
      (node (ref "U4") (pin "E27") (pinfunction "VDD25A_1_E27") (pintype "passive"))
      (node (ref "U4") (pin "E29") (pinfunction "VDD25A_2_E29") (pintype "passive"))
      (node (ref "U4") (pin "E31") (pinfunction "VDD25A_3_E31") (pintype "passive"))
      (node (ref "U4") (pin "E33") (pinfunction "VDD25A_4_E33") (pintype "passive"))
      (node (ref "U4") (pin "E35") (pinfunction "VDD25A_5_E35") (pintype "passive"))
      (node (ref "U4") (pin "E37") (pinfunction "VDD25A_6_E37") (pintype "passive"))
    )
    (net (code "33") (name "unconnected-(C646-Pad2)") (class "Default")
      (node (ref "C646") (pin "2") (pinfunction "2_2") (pintype "passive"))
    )
    (net (code "34") (name "unconnected-(C647-Pad2)") (class "Default")
      (node (ref "C647") (pin "2") (pinfunction "2_2") (pintype "passive"))
    )
    (net (code "35") (name "unconnected-(C648-Pad2)") (class "Default")
      (node (ref "C648") (pin "2") (pinfunction "2_2") (pintype "passive"))
    )
    (net (code "36") (name "unconnected-(C662-Pad1)") (class "Default")
      (node (ref "C662") (pin "1") (pinfunction "1_1") (pintype "passive"))
    )
    (net (code "37") (name "unconnected-(C663-Pad1)") (class "Default")
      (node (ref "C663") (pin "1") (pinfunction "1_1") (pintype "passive"))
    )
    (net (code "38") (name "unconnected-(C664-Pad1)") (class "Default")
      (node (ref "C664") (pin "1") (pinfunction "1_1") (pintype "passive"))
    )
    (net (code "39") (name "unconnected-(IC37-A1-Pad1)") (class "Default")
      (node (ref "IC37") (pin "1") (pinfunction "A1_1") (pintype "passive"))
    )
    (net (code "40") (name "unconnected-(IC37-A2-Pad3)") (class "Default")
      (node (ref "IC37") (pin "3") (pinfunction "A2_3") (pintype "passive"))
    )
    (net (code "41") (name "unconnected-(IC37-A3-Pad4)") (class "Default")
      (node (ref "IC37") (pin "4") (pinfunction "A3_4") (pintype "passive"))
    )
    (net (code "42") (name "unconnected-(IC37-A4-Pad5)") (class "Default")
      (node (ref "IC37") (pin "5") (pinfunction "A4_5") (pintype "passive"))
    )
    (net (code "43") (name "unconnected-(IC37-A5-Pad6)") (class "Default")
      (node (ref "IC37") (pin "6") (pinfunction "A5_6") (pintype "passive"))
    )
    (net (code "44") (name "unconnected-(IC37-A6-Pad7)") (class "Default")
      (node (ref "IC37") (pin "7") (pinfunction "A6_7") (pintype "passive"))
    )
    (net (code "45") (name "unconnected-(IC37-A7-Pad8)") (class "Default")
      (node (ref "IC37") (pin "8") (pinfunction "A7_8") (pintype "passive"))
    )
    (net (code "46") (name "unconnected-(IC37-A8-Pad9)") (class "Default")
      (node (ref "IC37") (pin "9") (pinfunction "A8_9") (pintype "passive"))
    )
    (net (code "47") (name "unconnected-(IC37-B1-Pad20)") (class "Default")
      (node (ref "IC37") (pin "20") (pinfunction "B1_20") (pintype "passive"))
    )
    (net (code "48") (name "unconnected-(IC37-B2-Pad18)") (class "Default")
      (node (ref "IC37") (pin "18") (pinfunction "B2_18") (pintype "passive"))
    )
    (net (code "49") (name "unconnected-(IC37-B3-Pad17)") (class "Default")
      (node (ref "IC37") (pin "17") (pinfunction "B3_17") (pintype "passive"))
    )
    (net (code "50") (name "unconnected-(IC37-B4-Pad16)") (class "Default")
      (node (ref "IC37") (pin "16") (pinfunction "B4_16") (pintype "passive"))
    )
    (net (code "51") (name "unconnected-(IC37-B5-Pad15)") (class "Default")
      (node (ref "IC37") (pin "15") (pinfunction "B5_15") (pintype "passive"))
    )
    (net (code "52") (name "unconnected-(IC37-B6-Pad14)") (class "Default")
      (node (ref "IC37") (pin "14") (pinfunction "B6_14") (pintype "passive"))
    )
    (net (code "53") (name "unconnected-(IC37-B7-Pad13)") (class "Default")
      (node (ref "IC37") (pin "13") (pinfunction "B7_13") (pintype "passive"))
    )
    (net (code "54") (name "unconnected-(IC37-B8-Pad12)") (class "Default")
      (node (ref "IC37") (pin "12") (pinfunction "B8_12") (pintype "passive"))
    )
    (net (code "55") (name "unconnected-(IC37-EP-Pad21)") (class "Default")
      (node (ref "IC37") (pin "21") (pinfunction "EP_21") (pintype "passive"))
    )
    (net (code "56") (name "unconnected-(IC37-GND-Pad11)") (class "Default")
      (node (ref "IC37") (pin "11") (pinfunction "GND_11") (pintype "passive"))
    )
    (net (code "57") (name "unconnected-(IC37-OE-Pad10)") (class "Default")
      (node (ref "IC37") (pin "10") (pinfunction "OE_10") (pintype "passive"))
    )
    (net (code "58") (name "unconnected-(IC37-VCCA-Pad2)") (class "Default")
      (node (ref "IC37") (pin "2") (pinfunction "VCCA_2") (pintype "passive"))
    )
    (net (code "59") (name "unconnected-(IC37-VCCB-Pad19)") (class "Default")
      (node (ref "IC37") (pin "19") (pinfunction "VCCB_19") (pintype "passive"))
    )
    (net (code "60") (name "unconnected-(U4E-GPIO0-PadD19)") (class "Default")
      (node (ref "U4") (pin "D19") (pinfunction "GPIO0_D19") (pintype "passive+no_connect"))
    )
    (net (code "61") (name "unconnected-(U4E-GPIO1-PadC14)") (class "Default")
      (node (ref "U4") (pin "C14") (pinfunction "GPIO1_C14") (pintype "passive+no_connect"))
    )
    (net (code "62") (name "unconnected-(U4E-GPIO2-PadD20)") (class "Default")
      (node (ref "U4") (pin "D20") (pinfunction "GPIO2_D20") (pintype "passive+no_connect"))
    )
    (net (code "63") (name "unconnected-(U4E-GPIO3-PadC15)") (class "Default")
      (node (ref "U4") (pin "C15") (pinfunction "GPIO3_C15") (pintype "passive+no_connect"))
    )
    (net (code "64") (name "unconnected-(U4E-GPIO4-PadB9)") (class "Default")
      (node (ref "U4") (pin "B9") (pinfunction "GPIO4_B9") (pintype "passive+no_connect"))
    )
    (net (code "65") (name "unconnected-(U4E-GPIO5-PadC16)") (class "Default")
      (node (ref "U4") (pin "C16") (pinfunction "GPIO5_C16") (pintype "passive+no_connect"))
    )
    (net (code "66") (name "unconnected-(U4E-GPIO6-PadD21)") (class "Default")
      (node (ref "U4") (pin "D21") (pinfunction "GPIO6_D21") (pintype "passive+no_connect"))
    )
    (net (code "67") (name "unconnected-(U4E-GPIO7-PadB10)") (class "Default")
      (node (ref "U4") (pin "B10") (pinfunction "GPIO7_B10") (pintype "passive+no_connect"))
    )
    (net (code "68") (name "unconnected-(U4E-GPIO8-PadC17)") (class "Default")
      (node (ref "U4") (pin "C17") (pinfunction "GPIO8_C17") (pintype "passive+no_connect"))
    )
    (net (code "69") (name "unconnected-(U4E-GPIO10-PadD24)") (class "Default")
      (node (ref "U4") (pin "D24") (pinfunction "GPIO10_D24") (pintype "passive+no_connect"))
    )
    (net (code "70") (name "unconnected-(U4E-GPIO11-PadD23)") (class "Default")
      (node (ref "U4") (pin "D23") (pinfunction "GPIO11_D23") (pintype "passive+no_connect"))
    )
    (net (code "71") (name "unconnected-(U4E-GPIO12-PadC18)") (class "Default")
      (node (ref "U4") (pin "C18") (pinfunction "GPIO12_C18") (pintype "passive+no_connect"))
    )
    (net (code "72") (name "unconnected-(U4E-GPIO13-PadB11)") (class "Default")
      (node (ref "U4") (pin "B11") (pinfunction "GPIO13_B11") (pintype "passive+no_connect"))
    )
    (net (code "73") (name "unconnected-(U4E-GPIO14-PadD25)") (class "Default")
      (node (ref "U4") (pin "D25") (pinfunction "GPIO14_D25") (pintype "passive+no_connect"))
    )
    (net (code "74") (name "unconnected-(U4E-NC_A1-PadA1)") (class "Default")
      (node (ref "U4") (pin "A1") (pinfunction "NC_A1_A1") (pintype "passive+no_connect"))
    )
    (net (code "75") (name "unconnected-(U4E-NC_A4-PadA4)") (class "Default")
      (node (ref "U4") (pin "A4") (pinfunction "NC_A4_A4") (pintype "passive+no_connect"))
    )
    (net (code "76") (name "unconnected-(U4E-NC_A5-PadA5)") (class "Default")
      (node (ref "U4") (pin "A5") (pinfunction "NC_A5_A5") (pintype "passive+no_connect"))
    )
    (net (code "77") (name "unconnected-(U4E-NC_A6-PadA6)") (class "Default")
      (node (ref "U4") (pin "A6") (pinfunction "NC_A6_A6") (pintype "passive+no_connect"))
    )
    (net (code "78") (name "unconnected-(U4E-RESERVED_1-PadC12)") (class "Default")
      (node (ref "U4") (pin "C12") (pinfunction "RESERVED_1_C12") (pintype "passive+no_connect"))
    )
    (net (code "79") (name "unconnected-(U4E-RESERVED_2-PadC13)") (class "Default")
      (node (ref "U4") (pin "C13") (pinfunction "RESERVED_2_C13") (pintype "passive+no_connect"))
    )
    (net (code "80") (name "unconnected-(U4E-RESERVED_3-PadD28)") (class "Default")
      (node (ref "U4") (pin "D28") (pinfunction "RESERVED_3_D28") (pintype "passive+no_connect"))
    )
    (net (code "81") (name "unconnected-(U4E-RESERVED_4-PadB14)") (class "Default")
      (node (ref "U4") (pin "B14") (pinfunction "RESERVED_4_B14") (pintype "passive+no_connect"))
    )
    (net (code "82") (name "unconnected-(U4E-RESERVED_5-PadB13)") (class "Default")
      (node (ref "U4") (pin "B13") (pinfunction "RESERVED_5_B13") (pintype "passive+no_connect"))
    )
    (net (code "83") (name "unconnected-(U4E-RESERVED_6-PadC20)") (class "Default")
      (node (ref "U4") (pin "C20") (pinfunction "RESERVED_6_C20") (pintype "passive+no_connect"))
    )
    (net (code "84") (name "unconnected-(U4E-RESERVED_7-PadD27)") (class "Default")
      (node (ref "U4") (pin "D27") (pinfunction "RESERVED_7_D27") (pintype "passive+no_connect"))
    )
    (net (code "85") (name "unconnected-(U4E-THERMDA-PadB1)") (class "Default")
      (node (ref "U4") (pin "B1") (pinfunction "THERMDA_B1") (pintype "passive+no_connect"))
    )
    (net (code "86") (name "unconnected-(U4E-THERMDC_VSS-PadD3)") (class "Default")
      (node (ref "U4") (pin "D3") (pinfunction "THERMDC_VSS_D3") (pintype "passive+no_connect"))
    )
  )
)
